# RFID-ArduinoBreakoutBoard.net
KiCad netlist of a schematic drawn in EAGLE
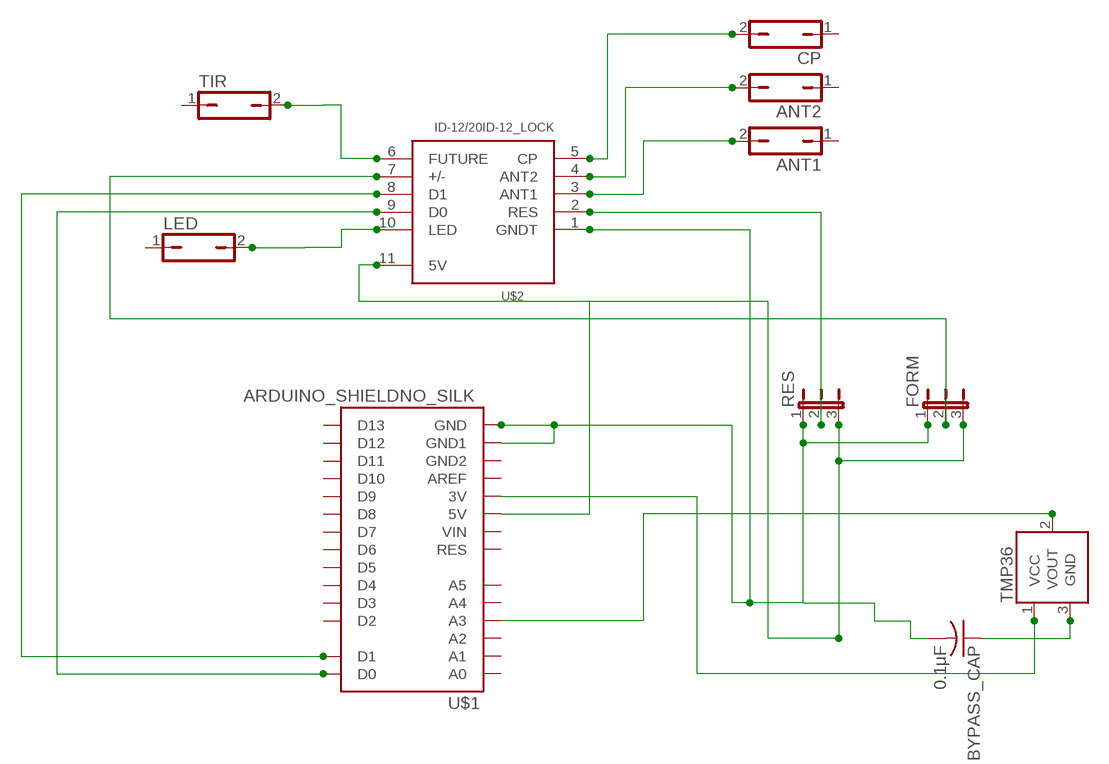
[diagram p0: schematic, sheet 1]

(export (version "E")
  (design (tool "Eeschema 10.0.6"))
  (components
    (comp (ref "ANT1")
      (value "JP1Q")
      (footprint "eagle-import:JP1")
      (libsource (lib "eagle-import") (part "JP1Q"))
    )
    (comp (ref "ANT2")
      (value "JP1Q")
      (footprint "eagle-import:JP1")
      (libsource (lib "eagle-import") (part "JP1Q"))
    )
    (comp (ref "BYPASS_CAP")
      (value "0.1μF")
      (footprint "eagle-import:C0805")
      (libsource (lib "eagle-import") (part "C-USC0805"))
    )
    (comp (ref "CP")
      (value "JP1Q")
      (footprint "eagle-import:JP1")
      (libsource (lib "eagle-import") (part "JP1Q"))
    )
    (comp (ref "FORM")
      (value "JP2W")
      (footprint "eagle-import:JP2W")
      (libsource (lib "eagle-import") (part "JP2W"))
    )
    (comp (ref "LED")
      (value "JP1Q")
      (footprint "eagle-import:JP1")
      (libsource (lib "eagle-import") (part "JP1Q"))
    )
    (comp (ref "RES")
      (value "JP2W")
      (footprint "eagle-import:JP2W")
      (libsource (lib "eagle-import") (part "JP2W"))
    )
    (comp (ref "TIR")
      (value "JP1Q")
      (footprint "eagle-import:JP1")
      (libsource (lib "eagle-import") (part "JP1Q"))
    )
    (comp (ref "TMP36")
      (value "TMP36GT9")
      (footprint "eagle-import:TO-92")
      (libsource (lib "eagle-import") (part "TMP36GT9"))
    )
    (comp (ref "U$1")
      (value "ARDUINO_SHIELDNO_SILK")
      (footprint "eagle-import:DUEMILANOVE_VIAS")
      (libsource (lib "eagle-import") (part "ARDUINO_SHIELDNO_SILK"))
    )
    (comp (ref "U$2")
      (value "ID-12/20ID-12_LOCK")
      (footprint "eagle-import:ID-12_LOCK")
      (libsource (lib "eagle-import") (part "ID-12/20ID-12_LOCK"))
    )
  )
  (nets
    (net (code "1") (name "Net-(TMP36-GND)") (class "Default")
      (node (ref "BYPASS_CAP") (pin "1") (pinfunction "1_1") (pintype "passive"))
      (node (ref "TMP36") (pin "3") (pinfunction "GND_3") (pintype "bidirectional"))
    )
    (net (code "2") (name "Net-(TMP36-VCC)") (class "Default")
      (node (ref "TMP36") (pin "1") (pinfunction "VCC_1") (pintype "bidirectional"))
      (node (ref "U$1") (pin "3.3V") (pinfunction "3V_3.3V") (pintype "bidirectional"))
    )
    (net (code "3") (name "Net-(TMP36-VOUT)") (class "Default")
      (node (ref "TMP36") (pin "2") (pinfunction "VOUT_2") (pintype "bidirectional"))
      (node (ref "U$1") (pin "A3") (pinfunction "A3_A3") (pintype "bidirectional"))
    )
    (net (code "4") (name "Net-(U$2-+{slash}-)") (class "Default")
      (node (ref "FORM") (pin "2") (pinfunction "2_2") (pintype "passive"))
      (node (ref "U$2") (pin "7") (pinfunction "+/-_7") (pintype "bidirectional"))
    )
    (net (code "5") (name "Net-(U$2-5V)") (class "Default")
      (node (ref "FORM") (pin "3") (pinfunction "3_3") (pintype "passive"))
      (node (ref "RES") (pin "3") (pinfunction "3_3") (pintype "passive"))
      (node (ref "U$1") (pin "5V") (pinfunction "5V_5V") (pintype "bidirectional"))
      (node (ref "U$2") (pin "11") (pinfunction "5V_11") (pintype "bidirectional"))
    )
    (net (code "6") (name "Net-(U$2-ANT1)") (class "Default")
      (node (ref "ANT1") (pin "2") (pinfunction "2_2") (pintype "passive"))
      (node (ref "U$2") (pin "3") (pinfunction "ANT1_3") (pintype "bidirectional"))
    )
    (net (code "7") (name "Net-(U$2-ANT2)") (class "Default")
      (node (ref "ANT2") (pin "2") (pinfunction "2_2") (pintype "passive"))
      (node (ref "U$2") (pin "4") (pinfunction "ANT2_4") (pintype "bidirectional"))
    )
    (net (code "8") (name "Net-(U$2-CP)") (class "Default")
      (node (ref "CP") (pin "2") (pinfunction "2_2") (pintype "passive"))
      (node (ref "U$2") (pin "5") (pinfunction "CP_5") (pintype "bidirectional"))
    )
    (net (code "9") (name "Net-(U$2-D0)") (class "Default")
      (node (ref "U$1") (pin "D0") (pinfunction "D0_D0") (pintype "bidirectional"))
      (node (ref "U$2") (pin "9") (pinfunction "D0_9") (pintype "bidirectional"))
    )
    (net (code "10") (name "Net-(U$2-D1)") (class "Default")
      (node (ref "U$1") (pin "D1") (pinfunction "D1_D1") (pintype "bidirectional"))
      (node (ref "U$2") (pin "8") (pinfunction "D1_8") (pintype "bidirectional"))
    )
    (net (code "11") (name "Net-(U$2-FUTURE)") (class "Default")
      (node (ref "TIR") (pin "2") (pinfunction "2_2") (pintype "passive"))
      (node (ref "U$2") (pin "6") (pinfunction "FUTURE_6") (pintype "bidirectional"))
    )
    (net (code "12") (name "Net-(U$2-GNDT)") (class "Default")
      (node (ref "BYPASS_CAP") (pin "2") (pinfunction "2_2") (pintype "passive"))
      (node (ref "FORM") (pin "1") (pinfunction "1_1") (pintype "passive"))
      (node (ref "RES") (pin "1") (pinfunction "1_1") (pintype "passive"))
      (node (ref "U$1") (pin "GND") (pinfunction "GND_GND") (pintype "bidirectional"))
      (node (ref "U$1") (pin "GND1") (pinfunction "GND1_GND1") (pintype "bidirectional"))
      (node (ref "U$2") (pin "1") (pinfunction "GNDT_1") (pintype "bidirectional"))
    )
    (net (code "13") (name "Net-(U$2-LED)") (class "Default")
      (node (ref "LED") (pin "2") (pinfunction "2_2") (pintype "passive"))
      (node (ref "U$2") (pin "10") (pinfunction "LED_10") (pintype "bidirectional"))
    )
    (net (code "14") (name "Net-(U$2-RES)") (class "Default")
      (node (ref "RES") (pin "2") (pinfunction "2_2") (pintype "passive"))
      (node (ref "U$2") (pin "2") (pinfunction "RES_2") (pintype "bidirectional"))
    )
    (net (code "15") (name "unconnected-(ANT1-Pad1)") (class "Default")
      (node (ref "ANT1") (pin "1") (pinfunction "1_1") (pintype "passive"))
    )
    (net (code "16") (name "unconnected-(ANT2-Pad1)") (class "Default")
      (node (ref "ANT2") (pin "1") (pinfunction "1_1") (pintype "passive"))
    )
    (net (code "17") (name "unconnected-(CP-Pad1)") (class "Default")
      (node (ref "CP") (pin "1") (pinfunction "1_1") (pintype "passive"))
    )
    (net (code "18") (name "unconnected-(LED-Pad1)") (class "Default")
      (node (ref "LED") (pin "1") (pinfunction "1_1") (pintype "passive"))
    )
    (net (code "19") (name "unconnected-(TIR-Pad1)") (class "Default")
      (node (ref "TIR") (pin "1") (pinfunction "1_1") (pintype "passive"))
    )
    (net (code "20") (name "unconnected-(U$1-PadA0)") (class "Default")
      (node (ref "U$1") (pin "A0") (pinfunction "A0_A0") (pintype "bidirectional"))
    )
    (net (code "21") (name "unconnected-(U$1-PadA1)") (class "Default")
      (node (ref "U$1") (pin "A1") (pinfunction "A1_A1") (pintype "bidirectional"))
    )
    (net (code "22") (name "unconnected-(U$1-PadA2)") (class "Default")
      (node (ref "U$1") (pin "A2") (pinfunction "A2_A2") (pintype "bidirectional"))
    )
    (net (code "23") (name "unconnected-(U$1-PadA4)") (class "Default")
      (node (ref "U$1") (pin "A4") (pinfunction "A4_A4") (pintype "bidirectional"))
    )
    (net (code "24") (name "unconnected-(U$1-PadA5)") (class "Default")
      (node (ref "U$1") (pin "A5") (pinfunction "A5_A5") (pintype "bidirectional"))
    )
    (net (code "25") (name "unconnected-(U$1-PadAREF)") (class "Default")
      (node (ref "U$1") (pin "AREF") (pinfunction "AREF_AREF") (pintype "bidirectional"))
    )
    (net (code "26") (name "unconnected-(U$1-PadD2)") (class "Default")
      (node (ref "U$1") (pin "D2") (pinfunction "D2_D2") (pintype "bidirectional"))
    )
    (net (code "27") (name "unconnected-(U$1-PadD3)") (class "Default")
      (node (ref "U$1") (pin "D3") (pinfunction "D3_D3") (pintype "bidirectional"))
    )
    (net (code "28") (name "unconnected-(U$1-PadD4)") (class "Default")
      (node (ref "U$1") (pin "D4") (pinfunction "D4_D4") (pintype "bidirectional"))
    )
    (net (code "29") (name "unconnected-(U$1-PadD5)") (class "Default")
      (node (ref "U$1") (pin "D5") (pinfunction "D5_D5") (pintype "bidirectional"))
    )
    (net (code "30") (name "unconnected-(U$1-PadD6)") (class "Default")
      (node (ref "U$1") (pin "D6") (pinfunction "D6_D6") (pintype "bidirectional"))
    )
    (net (code "31") (name "unconnected-(U$1-PadD7)") (class "Default")
      (node (ref "U$1") (pin "D7") (pinfunction "D7_D7") (pintype "bidirectional"))
    )
    (net (code "32") (name "unconnected-(U$1-PadD8)") (class "Default")
      (node (ref "U$1") (pin "D8") (pinfunction "D8_D8") (pintype "bidirectional"))
    )
    (net (code "33") (name "unconnected-(U$1-PadD9)") (class "Default")
      (node (ref "U$1") (pin "D9") (pinfunction "D9_D9") (pintype "bidirectional"))
    )
    (net (code "34") (name "unconnected-(U$1-PadD10)") (class "Default")
      (node (ref "U$1") (pin "D10") (pinfunction "D10_D10") (pintype "bidirectional"))
    )
    (net (code "35") (name "unconnected-(U$1-PadD11)") (class "Default")
      (node (ref "U$1") (pin "D11") (pinfunction "D11_D11") (pintype "bidirectional"))
    )
    (net (code "36") (name "unconnected-(U$1-PadD12)") (class "Default")
      (node (ref "U$1") (pin "D12") (pinfunction "D12_D12") (pintype "bidirectional"))
    )
    (net (code "37") (name "unconnected-(U$1-PadD13)") (class "Default")
      (node (ref "U$1") (pin "D13") (pinfunction "D13_D13") (pintype "bidirectional"))
    )
    (net (code "38") (name "unconnected-(U$1-PadGND2)") (class "Default")
      (node (ref "U$1") (pin "GND2") (pinfunction "GND2_GND2") (pintype "bidirectional"))
    )
    (net (code "39") (name "unconnected-(U$1-PadRES)") (class "Default")
      (node (ref "U$1") (pin "RES") (pinfunction "RES_RES") (pintype "bidirectional"))
    )
    (net (code "40") (name "unconnected-(U$1-PadVIN)") (class "Default")
      (node (ref "U$1") (pin "VIN") (pinfunction "VIN_VIN") (pintype "bidirectional"))
    )
  )
)
